# easyeda_pro_delay_module_2026-04-19.net
KiCad netlist of a schematic drawn in EasyEDA Pro
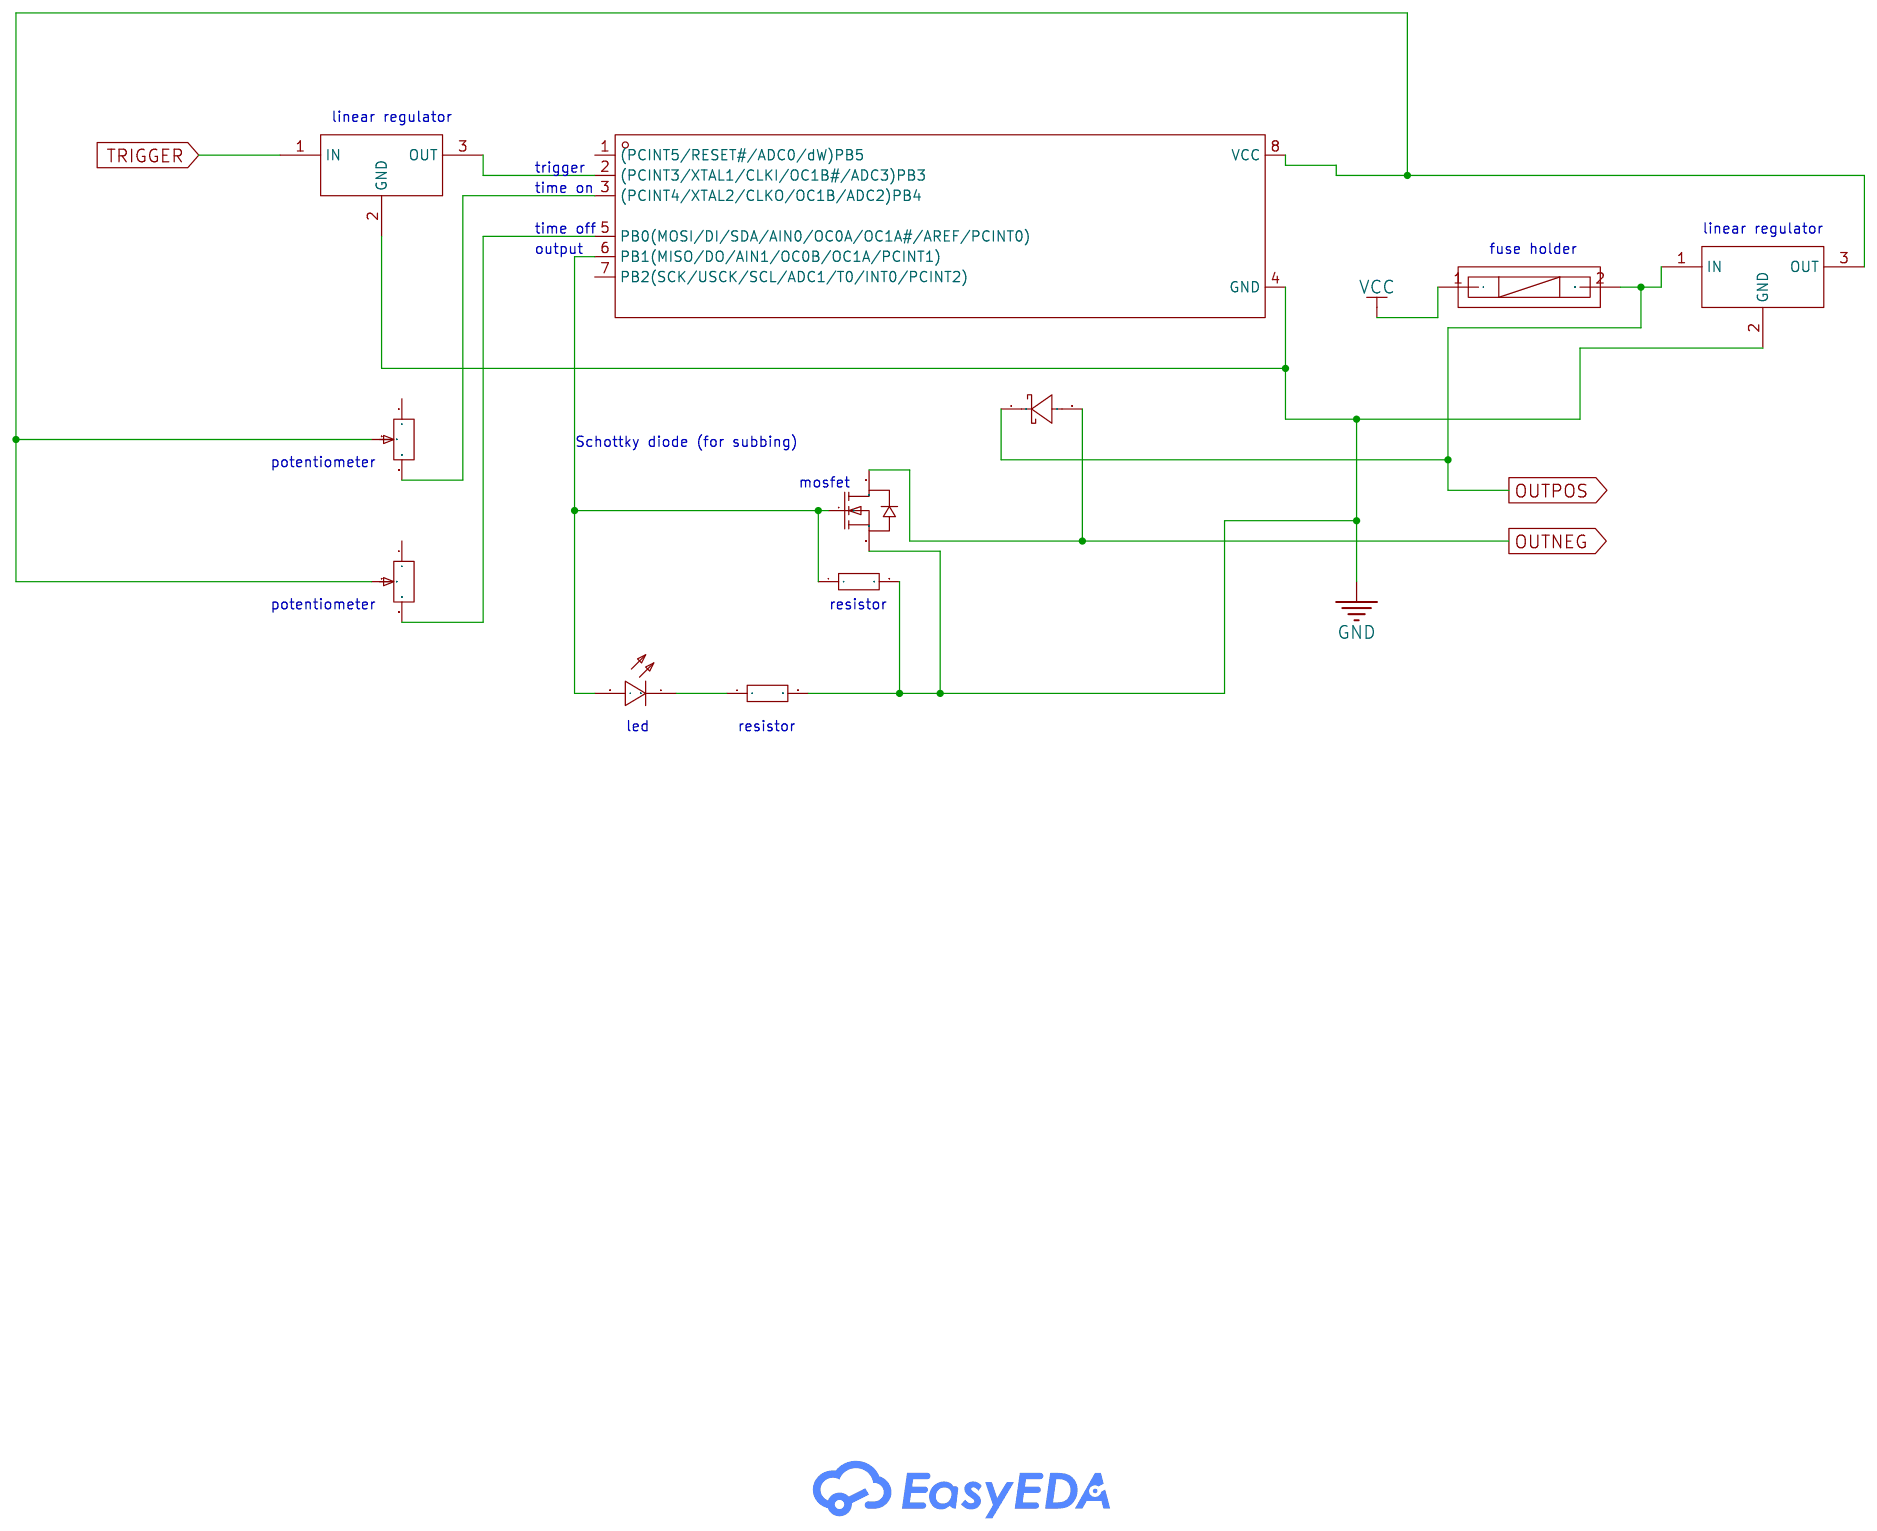
[diagram p0: schematic sheet]

(export (version "E")
  (design (tool "Eeschema 10.0.6"))
  (components
    (comp (ref "D1")
      (value "1N5819")
      (footprint "easyedapro:DO-41_BD2.4-L4.7-P8.70-D0.8-RD")
      (fields (field (name "Manufacturer") "luJing(鲁晶)"))
      (libsource (lib "easyedapro") (part "1N5819_C49318088"))
    )
    (comp (ref "F1")
      (value "5x20 BLX-A型 保险丝支架 XC-7")
      (footprint "easyedapro:FUSE-TH_L22.6-W9.0")
      (fields (field (name "Manufacturer") "xcfuse(旭程)"))
      (libsource (lib "easyedapro") (part "5x20 BLX-Atype Fuse holder XC-7"))
    )
    (comp (ref "IR1")
      (value "IR908-7C(E5)")
      (footprint "easyedapro:LED-TH_L4.5-W1.5-P2.54-RD")
      (fields (field (name "Manufacturer") "EVERLIGHT(亿光)"))
      (libsource (lib "easyedapro") (part "IR908-7C(E5)"))
    )
    (comp (ref "Q1")
      (value "FQP30N06L-VB")
      (footprint "easyedapro:TO-220AB-3_L10.3-W5.0-P2.54-L")
      (fields (field (name "Manufacturer") "VBsemi(微碧半导体)"))
      (libsource (lib "easyedapro") (part "FQP30N06L"))
    )
    (comp (ref "R1") (value "10K") (footprint "easyedapro:R0603") (libsource (lib "easyedapro") (part "Res")))
    (comp (ref "R2")
      (value "10kΩ")
      (footprint "easyedapro:RES-ADJ-TH_RK097111080J")
      (description "Resistance:10kΩ")
      (fields
        (field (name "Manufacturer Part") "RK097111080J")
        (field (name "Manufacturer") "ALPSALPINE(阿尔卑斯阿尔派)")
      )
      (libsource (lib "easyedapro") (part "RK097111080J"))
    )
    (comp (ref "R3")
      (value "10kΩ")
      (footprint "easyedapro:RES-ADJ-TH_RK097111080J")
      (description "Resistance:10kΩ")
      (fields
        (field (name "Manufacturer Part") "RK097111080J")
        (field (name "Manufacturer") "ALPSALPINE(阿尔卑斯阿尔派)")
      )
      (libsource (lib "easyedapro") (part "RK097111080J"))
    )
    (comp (ref "R4") (value "10K") (footprint "easyedapro:R0603") (libsource (lib "easyedapro") (part "Res")))
    (comp (ref "U1")
      (value "ATTINY85-20PU")
      (footprint "easyedapro:PDIP-8_L9.3-W6.4-P2.54-LS7.9-BL-1")
      (fields (field (name "Manufacturer") "MICROCHIP(美国微芯)"))
      (libsource (lib "easyedapro") (part "ATTINY85-20PU"))
    )
    (comp (ref "U2")
      (value "L7805CV")
      (footprint "easyedapro:TO-220-3_L10.0-W4.5-P2.54-L")
      (fields (field (name "Manufacturer") "GOODWORK(固得沃克)"))
      (libsource (lib "easyedapro") (part "L7805CV_C6430948"))
    )
    (comp (ref "U3")
      (value "L7805CV")
      (footprint "easyedapro:TO-220-3_L10.0-W4.5-P2.54-L")
      (fields (field (name "Manufacturer") "GOODWORK(固得沃克)"))
      (libsource (lib "easyedapro") (part "L7805CV_C6430948"))
    )
  )
  (nets
    (net (code "1") (name "GND") (class "Default")
      (node (ref "Q1") (pin "3") (pinfunction "S_3") (pintype "unspecified"))
      (node (ref "R1") (pin "2") (pinfunction "2_2") (pintype "input"))
      (node (ref "R4") (pin "2") (pinfunction "2_2") (pintype "input"))
      (node (ref "U1") (pin "4") (pinfunction "GND_4") (pintype "unspecified"))
      (node (ref "U2") (pin "2") (pinfunction "GND_2") (pintype "unspecified"))
      (node (ref "U3") (pin "2") (pinfunction "GND_2") (pintype "unspecified"))
    )
    (net (code "2") (name "Net-(IR1-A)") (class "Default")
      (node (ref "IR1") (pin "2") (pinfunction "A_2") (pintype "input"))
      (node (ref "Q1") (pin "1") (pinfunction "G_1") (pintype "unspecified"))
      (node (ref "R1") (pin "1") (pinfunction "1_1") (pintype "input"))
      (node (ref "U1") (pin "6") (pinfunction "PB1(MISO/DO/AIN1/OC0B/OC1A/PCINT1)_6") (pintype "unspecified"))
    )
    (net (code "3") (name "Net-(IR1-C)") (class "Default")
      (node (ref "IR1") (pin "1") (pinfunction "C_1") (pintype "input"))
      (node (ref "R4") (pin "1") (pinfunction "1_1") (pintype "input"))
    )
    (net (code "4") (name "Net-(U1-(PCINT3{slash}XTAL1{slash}CLKI{slash}OC1B#{slash}ADC3)PB3)") (class "Default")
      (node (ref "U1") (pin "2") (pinfunction "(PCINT3/XTAL1/CLKI/OC1B#/ADC3)PB3_2") (pintype "unspecified"))
      (node (ref "U2") (pin "3") (pinfunction "OUT_3") (pintype "unspecified"))
    )
    (net (code "5") (name "Net-(U1-(PCINT4{slash}XTAL2{slash}CLKO{slash}OC1B{slash}ADC2)PB4)") (class "Default")
      (node (ref "R2") (pin "3") (pinfunction "3_3") (pintype "input"))
      (node (ref "U1") (pin "3") (pinfunction "(PCINT4/XTAL2/CLKO/OC1B/ADC2)PB4_3") (pintype "unspecified"))
    )
    (net (code "6") (name "Net-(U1-PB0(MOSI{slash}DI{slash}SDA{slash}AIN0{slash}OC0A{slash}OC1A#{slash}AREF{slash}PCINT0))") (class "Default")
      (node (ref "R3") (pin "3") (pinfunction "3_3") (pintype "input"))
      (node (ref "U1") (pin "5") (pinfunction "PB0(MOSI/DI/SDA/AIN0/OC0A/OC1A#/AREF/PCINT0)_5") (pintype "unspecified"))
    )
    (net (code "7") (name "Net-(U1-VCC)") (class "Default")
      (node (ref "R2") (pin "2") (pinfunction "2_2") (pintype "input"))
      (node (ref "R3") (pin "2") (pinfunction "2_2") (pintype "input"))
      (node (ref "U1") (pin "8") (pinfunction "VCC_8") (pintype "unspecified"))
      (node (ref "U3") (pin "3") (pinfunction "OUT_3") (pintype "unspecified"))
    )
    (net (code "8") (name "OUTNEG") (class "Default")
      (node (ref "D1") (pin "2") (pinfunction "A_2") (pintype "unspecified"))
      (node (ref "Q1") (pin "2") (pinfunction "D_2") (pintype "unspecified"))
    )
    (net (code "9") (name "OUTPOS") (class "Default")
      (node (ref "D1") (pin "1") (pinfunction "C_1") (pintype "unspecified"))
      (node (ref "F1") (pin "2") (pinfunction "2_2") (pintype "unspecified"))
      (node (ref "U3") (pin "1") (pinfunction "IN_1") (pintype "unspecified"))
    )
    (net (code "10") (name "TRIGGER") (class "Default")
      (node (ref "U2") (pin "1") (pinfunction "IN_1") (pintype "unspecified"))
    )
    (net (code "11") (name "VCC") (class "Default")
      (node (ref "F1") (pin "1") (pinfunction "1_1") (pintype "unspecified"))
    )
    (net (code "12") (name "unconnected-(R2-Pad1)") (class "Default")
      (node (ref "R2") (pin "1") (pinfunction "1_1") (pintype "input"))
    )
    (net (code "13") (name "unconnected-(R3-Pad1)") (class "Default")
      (node (ref "R3") (pin "1") (pinfunction "1_1") (pintype "input"))
    )
    (net (code "14") (name "unconnected-(U1-(PCINT5{slash}RESET#{slash}ADC0{slash}dW)PB5-Pad1)") (class "Default")
      (node (ref "U1") (pin "1") (pinfunction "(PCINT5/RESET#/ADC0/dW)PB5_1") (pintype "unspecified"))
    )
    (net (code "15") (name "unconnected-(U1-PB2(SCK{slash}USCK{slash}SCL{slash}ADC1{slash}T0{slash}INT0{slash}PCINT2)-Pad7)") (class "Default")
      (node (ref "U1") (pin "7") (pinfunction "PB2(SCK/USCK/SCL/ADC1/T0/INT0/PCINT2)_7") (pintype "unspecified"))
    )
  )
)
